# sensie_v_0_0.net
KiCad netlist of a schematic drawn in Altium Designer
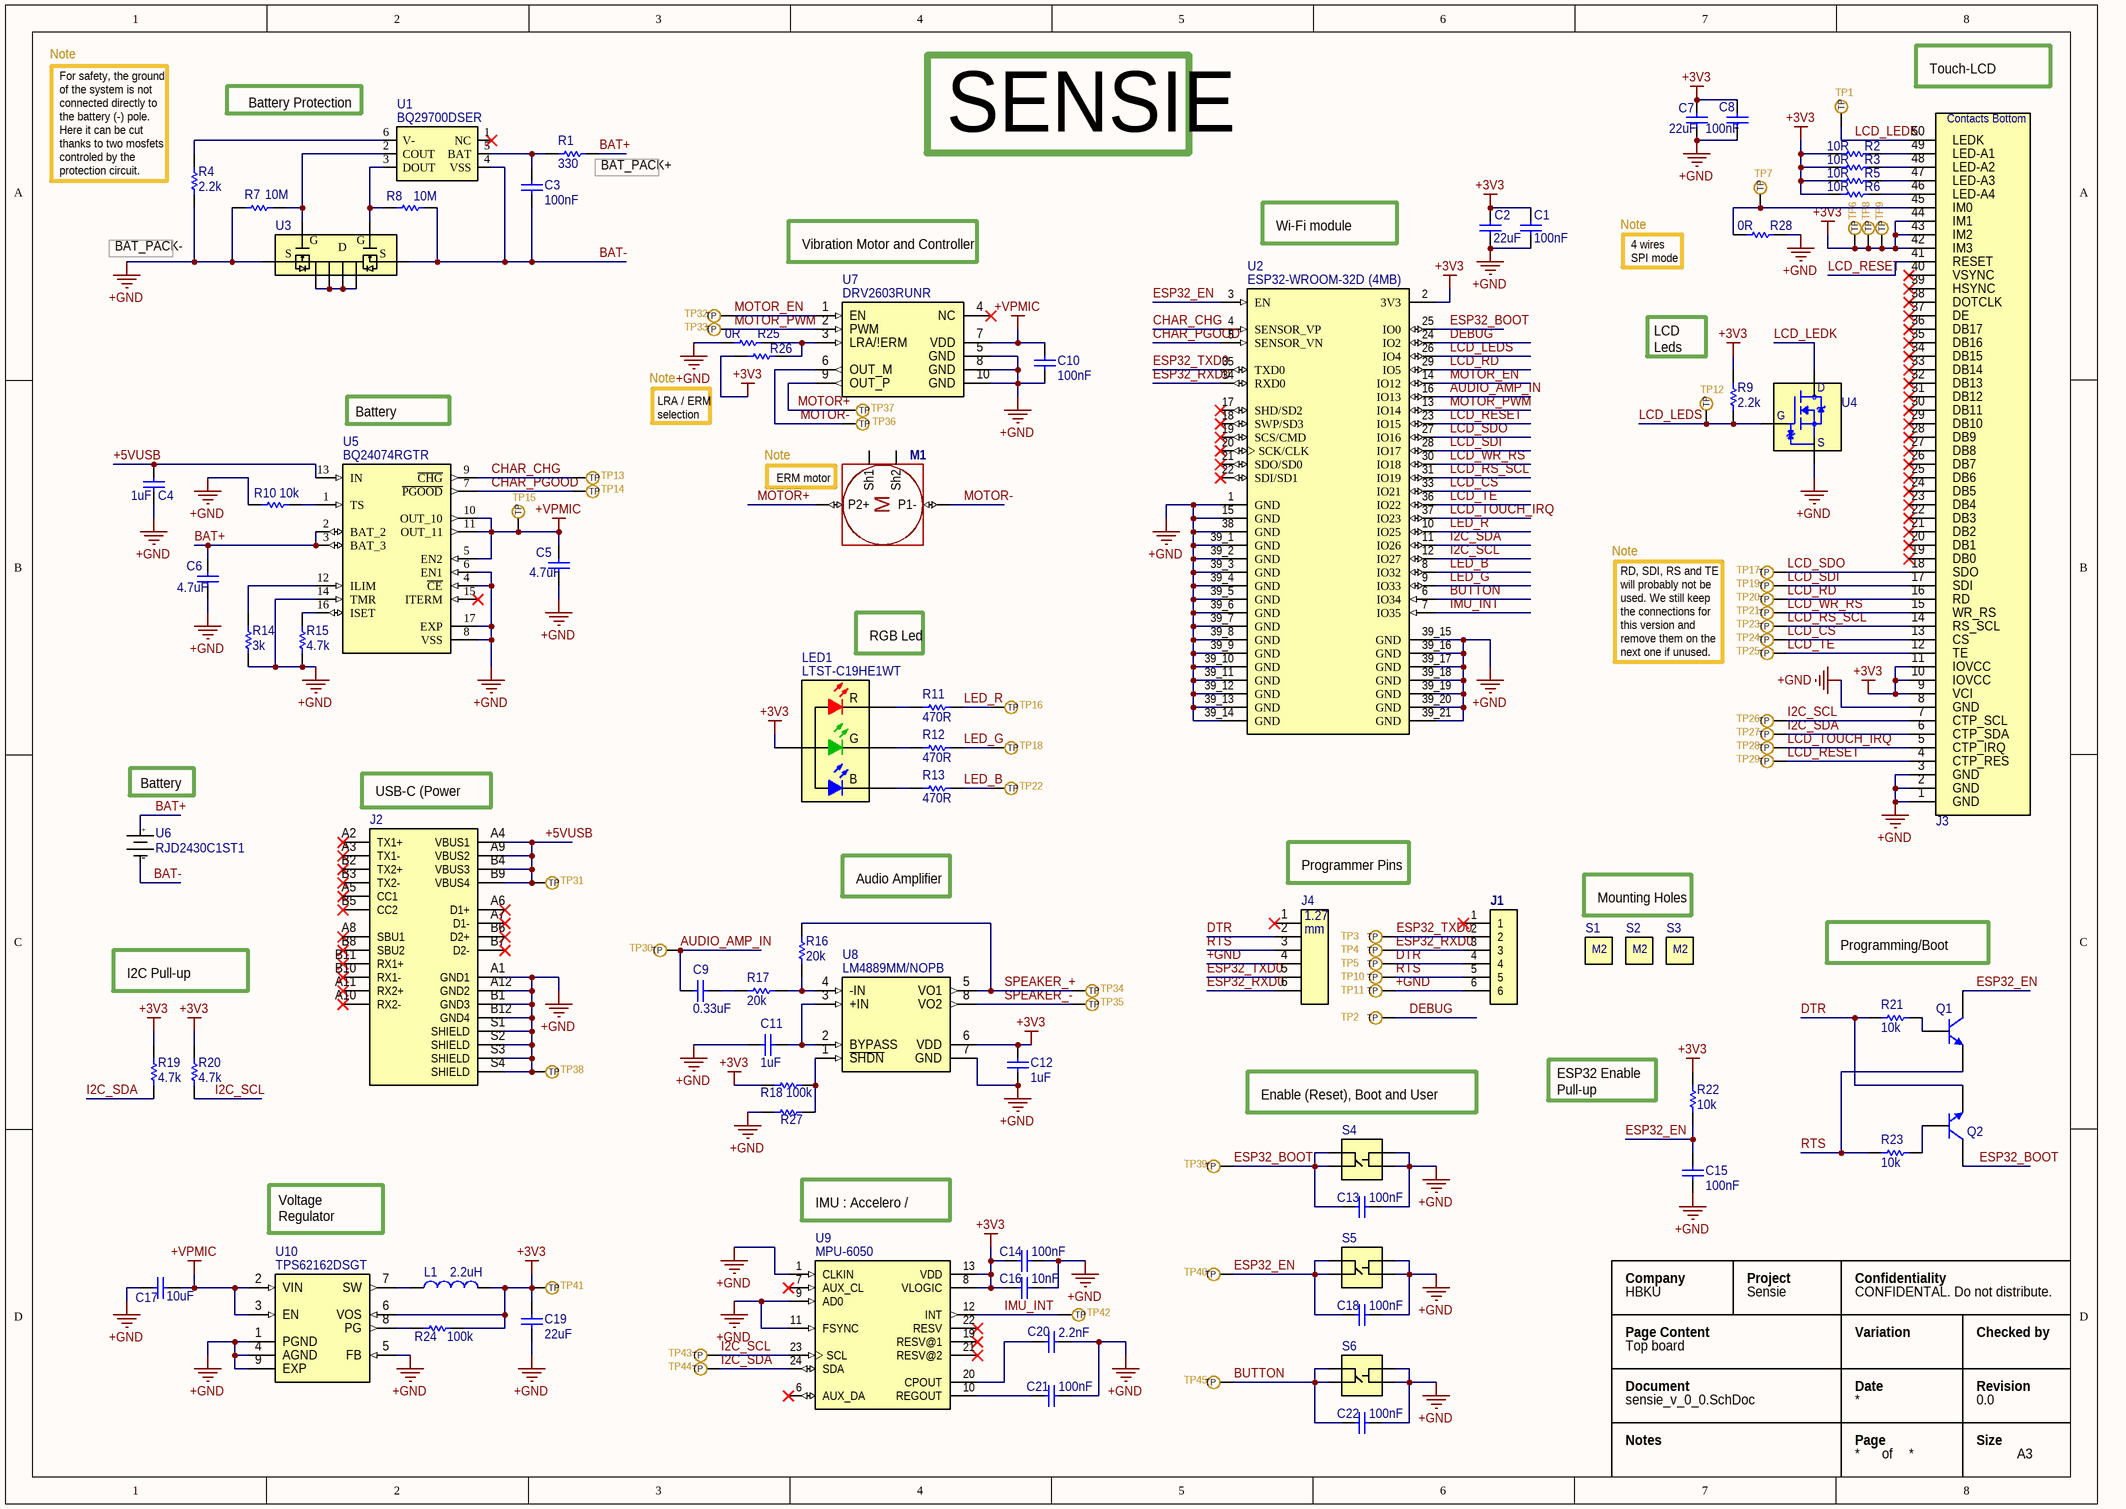
[diagram p0: sensie_v_0_0.SchDoc]

(export (version "E")
  (design (tool "Eeschema 10.0.6"))
  (components
    (comp (ref "C1")
      (value "100nF")
      (footprint "C0402")
      (description "CAP CER 0.1UF 16V X7R 0402")
      (fields
        (field (name "MANUFACTURER PART NUMBER") "GRM155R71C104KA88J")
        (field (name "MANUFACTURER") "Murata Electronics")
      )
      (libsource (lib "rcl") (part "CAP 100nF 0402"))
    )
    (comp (ref "C2")
      (value "22uF")
      (footprint "C0603")
      (description "CAP CER 22UF 6.3V X5R 0603")
      (fields
        (field (name "MANUFACTURER PART NUMBER") "GRM188R60J226MEA0D")
        (field (name "MANUFACTURER") "Murata Electronics")
      )
      (libsource (lib "rcl") (part "CAP 22uF 0603"))
    )
    (comp (ref "C3")
      (value "100nF")
      (footprint "C0402")
      (description "CAP CER 0.1UF 16V X7R 0402")
      (fields
        (field (name "MANUFACTURER PART NUMBER") "GRM155R71C104KA88J")
        (field (name "MANUFACTURER") "Murata Electronics")
      )
      (libsource (lib "rcl") (part "CAP 100nF 0402"))
    )
    (comp (ref "C4")
      (value "1uF")
      (footprint "C0402")
      (description "CAP CER 1UF 10V X6S 0402")
      (fields
        (field (name "MANUFACTURER PART NUMBER") "GRM155C81A105KA12D")
        (field (name "MANUFACTURER") "Murata Electronics")
      )
      (libsource (lib "rcl") (part "CAP 1uF 0402"))
    )
    (comp (ref "C5")
      (value "4.7uF")
      (footprint "C0402")
      (description "CAP CER 4.7UF 6.3V X5R 0402")
      (fields
        (field (name "MANUFACTURER PART NUMBER") "GRM155R60J475ME47D")
        (field (name "MANUFACTURER") "Murata Electronics")
      )
      (libsource (lib "rcl") (part "CAP 4.7uF 0402"))
    )
    (comp (ref "C6")
      (value "4.7uF")
      (footprint "C0402")
      (description "CAP CER 4.7UF 6.3V X5R 0402")
      (fields
        (field (name "MANUFACTURER PART NUMBER") "GRM155R60J475ME47D")
        (field (name "MANUFACTURER") "Murata Electronics")
      )
      (libsource (lib "rcl") (part "CAP 4.7uF 0402"))
    )
    (comp (ref "C7")
      (value "22uF")
      (footprint "C0603")
      (description "CAP CER 22UF 6.3V X5R 0603")
      (fields
        (field (name "MANUFACTURER PART NUMBER") "GRM188R60J226MEA0D")
        (field (name "MANUFACTURER") "Murata Electronics")
      )
      (libsource (lib "rcl") (part "CAP 22uF 0603"))
    )
    (comp (ref "C8")
      (value "100nF")
      (footprint "C0402")
      (description "CAP CER 0.1UF 16V X7R 0402")
      (fields
        (field (name "MANUFACTURER PART NUMBER") "GRM155R71C104KA88J")
        (field (name "MANUFACTURER") "Murata Electronics")
      )
      (libsource (lib "rcl") (part "CAP 100nF 0402"))
    )
    (comp (ref "C9")
      (value "0.33uF")
      (footprint "C0402")
      (description "CAP CER 0.33UF 10V X6S 0402")
      (fields
        (field (name "MANUFACTURER PART NUMBER") "GRM155R61A334KE15D")
        (field (name "MANUFACTURER") "Murata Electronics")
      )
      (libsource (lib "rcl") (part "CAP 0.33uF 0402"))
    )
    (comp (ref "C10")
      (value "100nF")
      (footprint "C0402")
      (description "CAP CER 0.1UF 16V X7R 0402")
      (fields
        (field (name "MANUFACTURER PART NUMBER") "GRM155R71C104KA88J")
        (field (name "MANUFACTURER") "Murata Electronics")
      )
      (libsource (lib "rcl") (part "CAP 100nF 0402"))
    )
    (comp (ref "C11")
      (value "1uF")
      (footprint "C0402")
      (description "CAP CER 1UF 10V X6S 0402")
      (fields
        (field (name "MANUFACTURER PART NUMBER") "GRM155C81A105KA12D")
        (field (name "MANUFACTURER") "Murata Electronics")
      )
      (libsource (lib "rcl") (part "CAP 1uF 0402"))
    )
    (comp (ref "C12")
      (value "1uF")
      (footprint "C0402")
      (description "CAP CER 1UF 10V X6S 0402")
      (fields
        (field (name "MANUFACTURER PART NUMBER") "GRM155C81A105KA12D")
        (field (name "MANUFACTURER") "Murata Electronics")
      )
      (libsource (lib "rcl") (part "CAP 1uF 0402"))
    )
    (comp (ref "C13")
      (value "100nF")
      (footprint "C0402")
      (description "CAP CER 0.1UF 16V X7R 0402")
      (fields
        (field (name "MANUFACTURER PART NUMBER") "GRM155R71C104KA88J")
        (field (name "MANUFACTURER") "Murata Electronics")
      )
      (libsource (lib "rcl") (part "CAP 100nF 0402"))
    )
    (comp (ref "C14")
      (value "100nF")
      (footprint "C0402")
      (description "CAP CER 0.1UF 16V X7R 0402")
      (fields
        (field (name "MANUFACTURER PART NUMBER") "GRM155R71C104KA88J")
        (field (name "MANUFACTURER") "Murata Electronics")
      )
      (libsource (lib "rcl") (part "CAP 100nF 0402"))
    )
    (comp (ref "C15")
      (value "100nF")
      (footprint "C0402")
      (description "CAP CER 0.1UF 16V X7R 0402")
      (fields
        (field (name "MANUFACTURER PART NUMBER") "GRM155R71C104KA88J")
        (field (name "MANUFACTURER") "Murata Electronics")
      )
      (libsource (lib "rcl") (part "CAP 100nF 0402"))
    )
    (comp (ref "C16")
      (value "10nF")
      (footprint "C0402")
      (description "CAP CER 10nF 16V X7R 0402")
      (fields
        (field (name "MANUFACTURER PART NUMBER") "GCM155R71H103KA55D")
        (field (name "MANUFACTURER") "Murata Electronics")
      )
      (libsource (lib "rcl") (part "CAP 10nF 0402"))
    )
    (comp (ref "C17")
      (value "10uF")
      (footprint "C0402")
      (description "CAP CER 10UF 4V X5R 0402")
      (fields
        (field (name "MANUFACTURER PART NUMBER") "GRM155R60G106ME44D")
        (field (name "MANUFACTURER") "Murata Electronics")
      )
      (libsource (lib "rcl") (part "CAP 10uF 0402"))
    )
    (comp (ref "C18")
      (value "100nF")
      (footprint "C0402")
      (description "CAP CER 0.1UF 16V X7R 0402")
      (fields
        (field (name "MANUFACTURER PART NUMBER") "GRM155R71C104KA88J")
        (field (name "MANUFACTURER") "Murata Electronics")
      )
      (libsource (lib "rcl") (part "CAP 100nF 0402"))
    )
    (comp (ref "C19")
      (value "22uF")
      (footprint "C0603")
      (description "CAP CER 22UF 6.3V X5R 0603")
      (fields
        (field (name "MANUFACTURER PART NUMBER") "GRM188R60J226MEA0D")
        (field (name "MANUFACTURER") "Murata Electronics")
      )
      (libsource (lib "rcl") (part "CAP 22uF 0603"))
    )
    (comp (ref "C20")
      (value "2.2nF")
      (footprint "C0402")
      (description "CAP CER 2.2nF 16V X7R 0402")
      (fields
        (field (name "MANUFACTURER PART NUMBER") "GCM155R72A222KA37D")
        (field (name "MANUFACTURER") "Murata Electronics")
      )
      (libsource (lib "rcl") (part "CAP 2.2nF 0402"))
    )
    (comp (ref "C21")
      (value "100nF")
      (footprint "C0402")
      (description "CAP CER 0.1UF 16V X7R 0402")
      (fields
        (field (name "MANUFACTURER PART NUMBER") "GRM155R71C104KA88J")
        (field (name "MANUFACTURER") "Murata Electronics")
      )
      (libsource (lib "rcl") (part "CAP 100nF 0402"))
    )
    (comp (ref "C22")
      (value "100nF")
      (footprint "C0402")
      (description "CAP CER 0.1UF 16V X7R 0402")
      (fields
        (field (name "MANUFACTURER PART NUMBER") "GRM155R71C104KA88J")
        (field (name "MANUFACTURER") "Murata Electronics")
      )
      (libsource (lib "rcl") (part "CAP 100nF 0402"))
    )
    (comp (ref "J1")
      (value "Plug of Nails 6 pins")
      (footprint "PLUG-OF-NAILS-6-PIN")
      (description "CBL PLUG-OF-NAILS 6-PIN with NO ATTACHMENT holes (contrary to the digikey link)")
      (fields
        (field (name "MANUFACTURER") "Tag-Connect LLC")
        (field (name "MANUFACTURER PART NUMBER") "TC2030-CTX")
      )
      (libsource (lib "connectors") (part "Plug of Nails 6 pins"))
    )
    (comp (ref "J2")
      (value "1054500101")
      (footprint "USB-C-1054500101")
      (description "USB-C CONN RCP USB3.1 TYPEC 24P SMD RA")
      (fields (field (name "MANUFACTURER") "Molex"))
      (libsource (lib "connectors") (part "1054500101"))
    )
    (comp (ref "J3")
      (value "FPC-50-screen-connector-bottom-62684-501100ALF")
      (footprint "FPC-50-62684-501100ALF")
      (description "FPC CONN BOTTOM 50POS 0.50MM R/A")
      (fields
        (field (name "MANUFACTURER") "Amphenol ICC (FCI)")
        (field (name "MANUFACTURER PART NUMBER") "62684-501100ALF")
      )
      (libsource (lib "connectors") (part "FPC-50-screen-connector-bottom-62684-501100ALF"))
    )
    (comp (ref "J4")
      (value "FTS-103-01-F-DV-TR")
      (footprint "CON_6_2_1.27_FTS_103_01")
      (description "CONN HEADER SMD 6POS 1.27MM")
      (fields (field (name "MANUFACTURER") "Samtec Inc."))
      (libsource (lib "connectors") (part "FTS-103-01-F-DV-TR"))
    )
    (comp (ref "L1")
      (value "2.2uH")
      (footprint "L0603")
      (description "2.2UH20% 1.05A(MAX) / 1.15A(TYP.")
      (fields
        (field (name "MANUFACTURER") "Murata Electronics")
        (field (name "MANUFACTURER PART NUMBER") "LQM18PN2R2MGHD")
      )
      (libsource (lib "rcl") (part "IND 2.2uH 0603"))
    )
    (comp (ref "LED1")
      (value "rgb_LTST-C19HE1WT")
      (footprint "LTST-C19HE1WT-4_V")
      (fields
        (field (name "MANUFACTURER") "Lite-On Inc.")
        (field (name "MANUFACTURER PART NUMBER") "LTST-C19HE1WT")
      )
      (libsource (lib "chips") (part "rgb_LTST-C19HE1WT"))
    )
    (comp (ref "M1")
      (value "MOTOR")
      (footprint "MOTOR")
      (description "VIBRATION MOTOR CYL 3V SMD")
      (fields
        (field (name "MANUFACTURER") "Jinlong Machinery & Electronics, Inc.")
        (field (name "MANUFACTURER PART NUMBER") "Z4FC1B1301781")
      )
      (libsource (lib "miscellaneaous") (part "MOTOR"))
    )
    (comp (ref "Q1")
      (value "MMBT2222ALT1G")
      (footprint "ONSC-SOT-23-3-318-08_V")
      (fields (field (name "MANUFACTURER") "ON Semiconductor"))
      (libsource (lib "chips") (part "MMBT2222ALT1G"))
    )
    (comp (ref "Q2")
      (value "MMBT2222ALT1G")
      (footprint "ONSC-SOT-23-3-318-08_V")
      (fields (field (name "MANUFACTURER") "ON Semiconductor"))
      (libsource (lib "chips") (part "MMBT2222ALT1G"))
    )
    (comp (ref "R1")
      (value "330")
      (footprint "R0402")
      (description "RES SMD 330 OHM 1% 1/16W 0402")
      (fields
        (field (name "MANUFACTURER") "Yageo")
        (field (name "MANUFACTURER PART NUMBER") "RC0402FR-07330RL")
      )
      (libsource (lib "rcl") (part "RES 330R 0402"))
    )
    (comp (ref "R2")
      (value "10R")
      (footprint "R0402")
      (description "RES SMD 10 OHM 1% 1/16W 0402")
      (fields
        (field (name "MANUFACTURER") "Yageo")
        (field (name "MANUFACTURER PART NUMBER") "RC0402FR-0710RL")
      )
      (libsource (lib "rcl") (part "RES 10R 0402"))
    )
    (comp (ref "R3")
      (value "10R")
      (footprint "R0402")
      (description "RES SMD 10 OHM 1% 1/16W 0402")
      (fields
        (field (name "MANUFACTURER") "Yageo")
        (field (name "MANUFACTURER PART NUMBER") "RC0402FR-0710RL")
      )
      (libsource (lib "rcl") (part "RES 10R 0402"))
    )
    (comp (ref "R4")
      (value "2.2k")
      (footprint "R0402")
      (description "RES SMD 2.2K OHM 1% 1/16W 0402")
      (fields
        (field (name "MANUFACTURER") "Yageo")
        (field (name "MANUFACTURER PART NUMBER") "RC0402FR-072K2L")
      )
      (libsource (lib "rcl") (part "RES 2.2k 0402"))
    )
    (comp (ref "R5")
      (value "10R")
      (footprint "R0402")
      (description "RES SMD 10 OHM 1% 1/16W 0402")
      (fields
        (field (name "MANUFACTURER") "Yageo")
        (field (name "MANUFACTURER PART NUMBER") "RC0402FR-0710RL")
      )
      (libsource (lib "rcl") (part "RES 10R 0402"))
    )
    (comp (ref "R6")
      (value "10R")
      (footprint "R0402")
      (description "RES SMD 10 OHM 1% 1/16W 0402")
      (fields
        (field (name "MANUFACTURER") "Yageo")
        (field (name "MANUFACTURER PART NUMBER") "RC0402FR-0710RL")
      )
      (libsource (lib "rcl") (part "RES 10R 0402"))
    )
    (comp (ref "R7")
      (value "10M")
      (footprint "R0402")
      (description "RES SMD 10 MOHM 1% 1/16W 0402")
      (fields
        (field (name "MANUFACTURER") "Yageo")
        (field (name "MANUFACTURER PART NUMBER") "RC0402FR-0710ML")
      )
      (libsource (lib "rcl") (part "RES 10M 0402"))
    )
    (comp (ref "R8")
      (value "10M")
      (footprint "R0402")
      (description "RES SMD 10 MOHM 1% 1/16W 0402")
      (fields
        (field (name "MANUFACTURER") "Yageo")
        (field (name "MANUFACTURER PART NUMBER") "RC0402FR-0710ML")
      )
      (libsource (lib "rcl") (part "RES 10M 0402"))
    )
    (comp (ref "R9")
      (value "2.2k")
      (footprint "R0402")
      (description "RES SMD 2.2K OHM 1% 1/16W 0402")
      (fields
        (field (name "MANUFACTURER") "Yageo")
        (field (name "MANUFACTURER PART NUMBER") "RC0402FR-072K2L")
      )
      (libsource (lib "rcl") (part "RES 2.2k 0402"))
    )
    (comp (ref "R10")
      (value "10k")
      (footprint "R0402")
      (description "RES SMD 10K OHM 1% 1/16W 0402")
      (fields
        (field (name "MANUFACTURER") "Yageo")
        (field (name "MANUFACTURER PART NUMBER") "RC0402FR-0710KL")
      )
      (libsource (lib "rcl") (part "RES 10k 0402"))
    )
    (comp (ref "R11")
      (value "470R")
      (footprint "R0402")
      (description "RES SMD 470 OHM 1% 1/16W 0402")
      (fields
        (field (name "MANUFACTURER") "Yageo")
        (field (name "MANUFACTURER PART NUMBER") "RC0402FR-07470RL")
      )
      (libsource (lib "rcl") (part "RES 470R 0402"))
    )
    (comp (ref "R12")
      (value "470R")
      (footprint "R0402")
      (description "RES SMD 470 OHM 1% 1/16W 0402")
      (fields
        (field (name "MANUFACTURER") "Yageo")
        (field (name "MANUFACTURER PART NUMBER") "RC0402FR-07470RL")
      )
      (libsource (lib "rcl") (part "RES 470R 0402"))
    )
    (comp (ref "R13")
      (value "470R")
      (footprint "R0402")
      (description "RES SMD 470 OHM 1% 1/16W 0402")
      (fields
        (field (name "MANUFACTURER") "Yageo")
        (field (name "MANUFACTURER PART NUMBER") "RC0402FR-07470RL")
      )
      (libsource (lib "rcl") (part "RES 470R 0402"))
    )
    (comp (ref "R14")
      (value "3k")
      (footprint "R0402")
      (description "RES SMD 10K OHM 1% 1/16W 0402")
      (fields
        (field (name "MANUFACTURER") "Yageo")
        (field (name "MANUFACTURER PART NUMBER") "RC0402FR-073KL")
      )
      (libsource (lib "rcl") (part "RES 3k 0402"))
    )
    (comp (ref "R15")
      (value "4.7k")
      (footprint "R0402")
      (description "RES SMD 4.7K OHM 1% 1/16W 0402")
      (fields
        (field (name "MANUFACTURER") "Yageo")
        (field (name "MANUFACTURER PART NUMBER") "RT0402FRE074K7L")
      )
      (libsource (lib "rcl") (part "RES 4.7k 0402"))
    )
    (comp (ref "R16")
      (value "20k")
      (footprint "R0402")
      (description "RES SMD 20K OHM 1% 1/16W 0402")
      (fields
        (field (name "MANUFACTURER") "Yageo")
        (field (name "MANUFACTURER PART NUMBER") "RC0402FR-0720KL")
      )
      (libsource (lib "rcl") (part "RES 20k 0402"))
    )
    (comp (ref "R17")
      (value "20k")
      (footprint "R0402")
      (description "RES SMD 20K OHM 1% 1/16W 0402")
      (fields
        (field (name "MANUFACTURER") "Yageo")
        (field (name "MANUFACTURER PART NUMBER") "RC0402FR-0720KL")
      )
      (libsource (lib "rcl") (part "RES 20k 0402"))
    )
    (comp (ref "R18")
      (value "100k")
      (footprint "R0402")
      (description "RES SMD 100K OHM 1% 1/16W 0402")
      (fields
        (field (name "MANUFACTURER") "Yageo")
        (field (name "MANUFACTURER PART NUMBER") "RC0402FR-07100KL")
      )
      (libsource (lib "rcl") (part "RES 100k 0402"))
    )
    (comp (ref "R19")
      (value "4.7k")
      (footprint "R0402")
      (description "RES SMD 4.7K OHM 1% 1/16W 0402")
      (fields
        (field (name "MANUFACTURER") "Yageo")
        (field (name "MANUFACTURER PART NUMBER") "RT0402FRE074K7L")
      )
      (libsource (lib "rcl") (part "RES 4.7k 0402"))
    )
    (comp (ref "R20")
      (value "4.7k")
      (footprint "R0402")
      (description "RES SMD 4.7K OHM 1% 1/16W 0402")
      (fields
        (field (name "MANUFACTURER") "Yageo")
        (field (name "MANUFACTURER PART NUMBER") "RT0402FRE074K7L")
      )
      (libsource (lib "rcl") (part "RES 4.7k 0402"))
    )
    (comp (ref "R21")
      (value "10k")
      (footprint "R0402")
      (description "RES SMD 10K OHM 1% 1/16W 0402")
      (fields
        (field (name "MANUFACTURER") "Yageo")
        (field (name "MANUFACTURER PART NUMBER") "RC0402FR-0710KL")
      )
      (libsource (lib "rcl") (part "RES 10k 0402"))
    )
    (comp (ref "R22")
      (value "10k")
      (footprint "R0402")
      (description "RES SMD 10K OHM 1% 1/16W 0402")
      (fields
        (field (name "MANUFACTURER") "Yageo")
        (field (name "MANUFACTURER PART NUMBER") "RC0402FR-0710KL")
      )
      (libsource (lib "rcl") (part "RES 10k 0402"))
    )
    (comp (ref "R23")
      (value "10k")
      (footprint "R0402")
      (description "RES SMD 10K OHM 1% 1/16W 0402")
      (fields
        (field (name "MANUFACTURER") "Yageo")
        (field (name "MANUFACTURER PART NUMBER") "RC0402FR-0710KL")
      )
      (libsource (lib "rcl") (part "RES 10k 0402"))
    )
    (comp (ref "R24")
      (value "100k")
      (footprint "R0402")
      (description "RES SMD 100K OHM 1% 1/16W 0402")
      (fields
        (field (name "MANUFACTURER") "Yageo")
        (field (name "MANUFACTURER PART NUMBER") "RC0402FR-07100KL")
      )
      (libsource (lib "rcl") (part "RES 100k 0402"))
    )
    (comp (ref "R25")
      (value "0R")
      (footprint "R0402")
      (description "RES SMD 0 OHM JUMPER 1/16W 0402")
      (fields
        (field (name "MANUFACTURER") "Yageo")
        (field (name "MANUFACTURER PART NUMBER") "RC0402JR-070RL")
      )
      (libsource (lib "rcl") (part "RES 0R 0402"))
    )
    (comp (ref "R26")
      (value "Thick Film")
      (footprint "R0402_DNI")
      (description "DNI (Do Not Install)")
      (libsource (lib "rcl") (part "RES DNI 0402"))
    )
    (comp (ref "R27")
      (value "Thick Film")
      (footprint "R0402_DNI")
      (description "DNI (Do Not Install)")
      (libsource (lib "rcl") (part "RES DNI 0402"))
    )
    (comp (ref "R28")
      (value "0R")
      (footprint "R0402")
      (description "RES SMD 0 OHM JUMPER 1/16W 0402")
      (fields
        (field (name "MANUFACTURER") "Yageo")
        (field (name "MANUFACTURER PART NUMBER") "RC0402JR-070RL")
      )
      (libsource (lib "rcl") (part "RES 0R 0402"))
    )
    (comp (ref "S1")
      (value "hole_M2")
      (footprint "M2_no_screw")
      (description "Mounting hole  M2 size, no solder stop, so no screw")
      (libsource (lib "connectors") (part "hole_M2"))
    )
    (comp (ref "S2")
      (value "hole_M2")
      (footprint "M2_no_screw")
      (description "Mounting hole  M2 size, no solder stop, so no screw")
      (libsource (lib "connectors") (part "hole_M2"))
    )
    (comp (ref "S3")
      (value "hole_M2")
      (footprint "M2_no_screw")
      (description "Mounting hole  M2 size, no solder stop, so no screw")
      (libsource (lib "connectors") (part "hole_M2"))
    )
    (comp (ref "S4")
      (value "TL1014BF160QG")
      (footprint "BUTTON_TL1014BF160QG")
      (description "SWITCH TACTILE SPST-NO 0.05A 12V")
      (fields (field (name "MANUFACTURER") "E-Switch"))
      (libsource (lib "miscellaneaous") (part "TL1014BF160QG"))
    )
    (comp (ref "S5")
      (value "TL1014BF160QG")
      (footprint "BUTTON_TL1014BF160QG")
      (description "SWITCH TACTILE SPST-NO 0.05A 12V")
      (fields (field (name "MANUFACTURER") "E-Switch"))
      (libsource (lib "miscellaneaous") (part "TL1014BF160QG"))
    )
    (comp (ref "S6")
      (value "TL1014BF160QG")
      (footprint "BUTTON_TL1014BF160QG")
      (description "SWITCH TACTILE SPST-NO 0.05A 12V")
      (fields (field (name "MANUFACTURER") "E-Switch"))
      (libsource (lib "miscellaneaous") (part "TL1014BF160QG"))
    )
    (comp (ref "TP1")
      (value "TP_1mm")
      (footprint "TP_1mm")
      (description "Test point 1mm diameter")
      (libsource (lib "miscellaneaous") (part "TP_1mm"))
    )
    (comp (ref "TP2")
      (value "TP_2mm")
      (footprint "TP_2mm")
      (description "Test point 2mm diameter")
      (libsource (lib "miscellaneaous") (part "TP_2mm"))
    )
    (comp (ref "TP3")
      (value "TP_2mm")
      (footprint "TP_2mm")
      (description "Test point 2mm diameter")
      (libsource (lib "miscellaneaous") (part "TP_2mm"))
    )
    (comp (ref "TP4")
      (value "TP_2mm")
      (footprint "TP_2mm")
      (description "Test point 2mm diameter")
      (libsource (lib "miscellaneaous") (part "TP_2mm"))
    )
    (comp (ref "TP5")
      (value "TP_2mm")
      (footprint "TP_2mm")
      (description "Test point 2mm diameter")
      (libsource (lib "miscellaneaous") (part "TP_2mm"))
    )
    (comp (ref "TP6")
      (value "TP_1mm")
      (footprint "TP_1mm")
      (description "Test point 1mm diameter")
      (libsource (lib "miscellaneaous") (part "TP_1mm"))
    )
    (comp (ref "TP7")
      (value "TP_1mm")
      (footprint "TP_1mm")
      (description "Test point 1mm diameter")
      (libsource (lib "miscellaneaous") (part "TP_1mm"))
    )
    (comp (ref "TP8")
      (value "TP_1mm")
      (footprint "TP_1mm")
      (description "Test point 1mm diameter")
      (libsource (lib "miscellaneaous") (part "TP_1mm"))
    )
    (comp (ref "TP9")
      (value "TP_1mm")
      (footprint "TP_1mm")
      (description "Test point 1mm diameter")
      (libsource (lib "miscellaneaous") (part "TP_1mm"))
    )
    (comp (ref "TP10")
      (value "TP_2mm")
      (footprint "TP_2mm")
      (description "Test point 2mm diameter")
      (libsource (lib "miscellaneaous") (part "TP_2mm"))
    )
    (comp (ref "TP11")
      (value "TP_2mm")
      (footprint "TP_2mm")
      (description "Test point 2mm diameter")
      (libsource (lib "miscellaneaous") (part "TP_2mm"))
    )
    (comp (ref "TP12")
      (value "TP_1mm")
      (footprint "TP_1mm")
      (description "Test point 1mm diameter")
      (libsource (lib "miscellaneaous") (part "TP_1mm"))
    )
    (comp (ref "TP13")
      (value "TP_1mm")
      (footprint "TP_1mm")
      (description "Test point 1mm diameter")
      (libsource (lib "miscellaneaous") (part "TP_1mm"))
    )
    (comp (ref "TP14")
      (value "TP_1mm")
      (footprint "TP_1mm")
      (description "Test point 1mm diameter")
      (libsource (lib "miscellaneaous") (part "TP_1mm"))
    )
    (comp (ref "TP15")
      (value "TP_1mm")
      (footprint "TP_1mm")
      (description "Test point 1mm diameter")
      (libsource (lib "miscellaneaous") (part "TP_1mm"))
    )
    (comp (ref "TP16")
      (value "TP_1mm")
      (footprint "TP_1mm")
      (description "Test point 1mm diameter")
      (libsource (lib "miscellaneaous") (part "TP_1mm"))
    )
    (comp (ref "TP17")
      (value "TP_1mm")
      (footprint "TP_1mm")
      (description "Test point 1mm diameter")
      (libsource (lib "miscellaneaous") (part "TP_1mm"))
    )
    (comp (ref "TP18")
      (value "TP_1mm")
      (footprint "TP_1mm")
      (description "Test point 1mm diameter")
      (libsource (lib "miscellaneaous") (part "TP_1mm"))
    )
    (comp (ref "TP19")
      (value "TP_1mm")
      (footprint "TP_1mm")
      (description "Test point 1mm diameter")
      (libsource (lib "miscellaneaous") (part "TP_1mm"))
    )
    (comp (ref "TP20")
      (value "TP_1mm")
      (footprint "TP_1mm")
      (description "Test point 1mm diameter")
      (libsource (lib "miscellaneaous") (part "TP_1mm"))
    )
    (comp (ref "TP21")
      (value "TP_1mm")
      (footprint "TP_1mm")
      (description "Test point 1mm diameter")
      (libsource (lib "miscellaneaous") (part "TP_1mm"))
    )
    (comp (ref "TP22")
      (value "TP_1mm")
      (footprint "TP_1mm")
      (description "Test point 1mm diameter")
      (libsource (lib "miscellaneaous") (part "TP_1mm"))
    )
    (comp (ref "TP23")
      (value "TP_1mm")
      (footprint "TP_1mm")
      (description "Test point 1mm diameter")
      (libsource (lib "miscellaneaous") (part "TP_1mm"))
    )
    (comp (ref "TP24")
      (value "TP_1mm")
      (footprint "TP_1mm")
      (description "Test point 1mm diameter")
      (libsource (lib "miscellaneaous") (part "TP_1mm"))
    )
    (comp (ref "TP25")
      (value "TP_1mm")
      (footprint "TP_1mm")
      (description "Test point 1mm diameter")
      (libsource (lib "miscellaneaous") (part "TP_1mm"))
    )
    (comp (ref "TP26")
      (value "TP_1mm")
      (footprint "TP_1mm")
      (description "Test point 1mm diameter")
      (libsource (lib "miscellaneaous") (part "TP_1mm"))
    )
    (comp (ref "TP27")
      (value "TP_1mm")
      (footprint "TP_1mm")
      (description "Test point 1mm diameter")
      (libsource (lib "miscellaneaous") (part "TP_1mm"))
    )
    (comp (ref "TP28")
      (value "TP_1mm")
      (footprint "TP_1mm")
      (description "Test point 1mm diameter")
      (libsource (lib "miscellaneaous") (part "TP_1mm"))
    )
    (comp (ref "TP29")
      (value "TP_1mm")
      (footprint "TP_1mm")
      (description "Test point 1mm diameter")
      (libsource (lib "miscellaneaous") (part "TP_1mm"))
    )
    (comp (ref "TP30")
      (value "TP_1mm")
      (footprint "TP_1mm")
      (description "Test point 1mm diameter")
      (libsource (lib "miscellaneaous") (part "TP_1mm"))
    )
    (comp (ref "TP31")
      (value "TP_1mm")
      (footprint "TP_1mm")
      (description "Test point 1mm diameter")
      (libsource (lib "miscellaneaous") (part "TP_1mm"))
    )
    (comp (ref "TP32")
      (value "TP_1mm")
      (footprint "TP_1mm")
      (description "Test point 1mm diameter")
      (libsource (lib "miscellaneaous") (part "TP_1mm"))
    )
    (comp (ref "TP33")
      (value "TP_1mm")
      (footprint "TP_1mm")
      (description "Test point 1mm diameter")
      (libsource (lib "miscellaneaous") (part "TP_1mm"))
    )
    (comp (ref "TP34")
      (value "TP_2mm")
      (footprint "TP_2mm")
      (description "Test point 2mm diameter")
      (libsource (lib "miscellaneaous") (part "TP_2mm"))
    )
    (comp (ref "TP35")
      (value "TP_2mm")
      (footprint "TP_2mm")
      (description "Test point 2mm diameter")
      (libsource (lib "miscellaneaous") (part "TP_2mm"))
    )
    (comp (ref "TP36")
      (value "TP_2mm")
      (footprint "TP_2mm")
      (description "Test point 2mm diameter")
      (libsource (lib "miscellaneaous") (part "TP_2mm"))
    )
    (comp (ref "TP37")
      (value "TP_2mm")
      (footprint "TP_2mm")
      (description "Test point 2mm diameter")
      (libsource (lib "miscellaneaous") (part "TP_2mm"))
    )
    (comp (ref "TP38")
      (value "TP_1mm")
      (footprint "TP_1mm")
      (description "Test point 1mm diameter")
      (libsource (lib "miscellaneaous") (part "TP_1mm"))
    )
    (comp (ref "TP39")
      (value "TP_1mm")
      (footprint "TP_1mm")
      (description "Test point 1mm diameter")
      (libsource (lib "miscellaneaous") (part "TP_1mm"))
    )
    (comp (ref "TP40")
      (value "TP_1mm")
      (footprint "TP_1mm")
      (description "Test point 1mm diameter")
      (libsource (lib "miscellaneaous") (part "TP_1mm"))
    )
    (comp (ref "TP41")
      (value "TP_1mm")
      (footprint "TP_1mm")
      (description "Test point 1mm diameter")
      (libsource (lib "miscellaneaous") (part "TP_1mm"))
    )
    (comp (ref "TP42")
      (value "TP_1mm")
      (footprint "TP_1mm")
      (description "Test point 1mm diameter")
      (libsource (lib "miscellaneaous") (part "TP_1mm"))
    )
    (comp (ref "TP43")
      (value "TP_1mm")
      (footprint "TP_1mm")
      (description "Test point 1mm diameter")
      (libsource (lib "miscellaneaous") (part "TP_1mm"))
    )
    (comp (ref "TP44")
      (value "TP_1mm")
      (footprint "TP_1mm")
      (description "Test point 1mm diameter")
      (libsource (lib "miscellaneaous") (part "TP_1mm"))
    )
    (comp (ref "TP45")
      (value "TP_1mm")
      (footprint "TP_1mm")
      (description "Test point 1mm diameter")
      (libsource (lib "miscellaneaous") (part "TP_1mm"))
    )
    (comp (ref "U1")
      (value "BQ29700DSER")
      (footprint "BATT_PROTEC_BQ29700DSER")
      (description "BATT LITHIUM BATT PROTECT 6-SON")
      (fields (field (name "MANUFACTURER") "Texas Instruments"))
      (libsource (lib "chips") (part "BQ29700DSER"))
    )
    (comp (ref "U2")
      (value "ESP32-WROOM-32D")
      (footprint "ESP32-WROOM-32D (4MB)")
      (description "ESP32-WROOM-32D Wifi/Bluetooth Module")
      (fields
        (field (name "MANUFACTURER") "Espressif Systems")
        (field (name "MANUFACTURER PART NUMBER") "ESP32-WROOM-32D (4MB)")
      )
      (libsource (lib "chips") (part "ESP32-WROOM-32D"))
    )
    (comp (ref "U3")
      (value "ECH8693R-TL-W")
      (footprint "MOSFET_2CHAN_ECH8693R-TL-W")
      (description "MOSFET 2N-CH 24V 14A SOT-28")
      (fields (field (name "MANUFACTURER") "ON Semiconductor"))
      (libsource (lib "chips") (part "ECH8693R-TL-W"))
    )
    (comp (ref "U4")
      (value "DMG1012UW-7")
      (footprint "MOSFET-DMG1012UW-SOT323")
      (description "MOSFET Logi level N-CH 20V 1A SOT323")
      (fields (field (name "MANUFACTURER") "Diodes Incorporated"))
      (libsource (lib "chips") (part "DMG1012UW-7"))
    )
    (comp (ref "U5")
      (value "BQ24074RGTR")
      (footprint "BATT_CHARG_BQ24074RGTR")
      (description "BATT LI-ION CHARGE MGMT 16-QFN")
      (fields
        (field (name "MANUFACTURER") "Texas Instruments")
        (field (name "MANUFACTURER PART NUMBER") "BQ24074RGTR")
      )
      (libsource (lib "chips") (part "BQ24074RGTR"))
    )
    (comp (ref "U6")
      (value "RJD2430C1ST1")
      (footprint "COIN_BAT_110_MAH_RJD2430C1ST1")
      (description "BATTERY LITHIUM 110mAh 3.7V COIN 24.5MM")
      (fields
        (field (name "MANUFACTURER") "Illinois Capacitor")
        (field (name "MANUFACTURER PART NUMBER") "RJD2430C1ST1")
      )
      (libsource (lib "miscellaneaous") (part "RJD2430C1ST1"))
    )
    (comp (ref "U7")
      (value "DRV2603RUNR")
      (footprint "MOT_DRV_DRV2603RUNR")
      (description "MOTOR DRIVER 2.5V-5.2V 10QFN")
      (fields (field (name "MANUFACTURER") "Texas Instruments"))
      (libsource (lib "chips") (part "DRV2603RUNR"))
    )
    (comp (ref "U8")
      (value "LM4889")
      (footprint "Amp_LM4889MM")
      (description "IC AMP CLASS AB MONO 1W 8VSSOP")
      (fields
        (field (name "MANUFACTURER") "Texas Instruments")
        (field (name "MANUFACTURER PART NUMBER") "LM4889MM/NOPB")
      )
      (libsource (lib "chips") (part "LM4889"))
    )
    (comp (ref "U9")
      (value "MPU-6050")
      (footprint "MPU6050-ACCELERO-GYRO")
      (description "IMU ACCEL/GYRO 3-AXIS I2C 24QFN")
      (fields
        (field (name "MANUFACTURER") "TDK InvenSense")
        (field (name "MANUFACTURER PART NUMBER") "MPU-6050")
      )
      (libsource (lib "chips") (part "MPU-6050"))
    )
    (comp (ref "U10")
      (value "TPS62162DSGT")
      (footprint "REG_BUCK_TPS62162DSGT")
      (description "IC REG BUCK 3.3V 1A 8WSON")
      (fields
        (field (name "MANUFACTURER") "Texas Instruments")
        (field (name "MANUFACTURER PART NUMBER") "TPS62162DSGT")
      )
      (libsource (lib "chips") (part "TPS62162DSGT"))
    )
  )
  (nets
    (net (code "1") (name "+3V3") (class "Default")
      (node (ref "C1") (pin "2") (pinfunction "2_2") (pintype "passive"))
      (node (ref "C12") (pin "2") (pinfunction "2_2") (pintype "passive"))
      (node (ref "C14") (pin "1") (pinfunction "1_1") (pintype "passive"))
      (node (ref "C16") (pin "1") (pinfunction "1_1") (pintype "passive"))
      (node (ref "C19") (pin "2") (pinfunction "2_2") (pintype "passive"))
      (node (ref "C2") (pin "2") (pinfunction "2_2") (pintype "passive"))
      (node (ref "C7") (pin "2") (pinfunction "2_2") (pintype "passive"))
      (node (ref "C8") (pin "2") (pinfunction "2_2") (pintype "passive"))
      (node (ref "J3") (pin "10") (pinfunction "IOVCC_10") (pintype "passive"))
      (node (ref "J3") (pin "11") (pinfunction "IOVCC_11") (pintype "passive"))
      (node (ref "J3") (pin "42") (pinfunction "IM3_42") (pintype "passive"))
      (node (ref "J3") (pin "43") (pinfunction "IM2_43") (pintype "passive"))
      (node (ref "J3") (pin "44") (pinfunction "IM1_44") (pintype "passive"))
      (node (ref "J3") (pin "9") (pinfunction "VCI_9") (pintype "passive"))
      (node (ref "L1") (pin "2") (pinfunction "2_2") (pintype "passive"))
      (node (ref "LED1") (pin "4") (pinfunction "A_4") (pintype "passive"))
      (node (ref "R18") (pin "1") (pinfunction "1_1") (pintype "passive"))
      (node (ref "R19") (pin "2") (pinfunction "2_2") (pintype "passive"))
      (node (ref "R2") (pin "1") (pinfunction "1_1") (pintype "passive"))
      (node (ref "R20") (pin "2") (pinfunction "2_2") (pintype "passive"))
      (node (ref "R22") (pin "2") (pinfunction "2_2") (pintype "passive"))
      (node (ref "R24") (pin "2") (pinfunction "2_2") (pintype "passive"))
      (node (ref "R26") (pin "1") (pinfunction "1_1") (pintype "passive"))
      (node (ref "R3") (pin "1") (pinfunction "1_1") (pintype "passive"))
      (node (ref "R5") (pin "1") (pinfunction "1_1") (pintype "passive"))
      (node (ref "R6") (pin "1") (pinfunction "1_1") (pintype "passive"))
      (node (ref "R9") (pin "2") (pinfunction "2_2") (pintype "passive"))
      (node (ref "TP41") (pin "1") (pinfunction "TP_1") (pintype "passive"))
      (node (ref "TP6") (pin "1") (pinfunction "TP_1") (pintype "passive"))
      (node (ref "TP8") (pin "1") (pinfunction "TP_1") (pintype "passive"))
      (node (ref "TP9") (pin "1") (pinfunction "TP_1") (pintype "passive"))
      (node (ref "U10") (pin "6") (pinfunction "VOS_6") (pintype "input"))
      (node (ref "U2") (pin "2") (pinfunction "3V3_2") (pintype "power_in"))
      (node (ref "U8") (pin "6") (pinfunction "VDD_6") (pintype "power_in"))
      (node (ref "U9") (pin "13") (pinfunction "VDD_13") (pintype "power_in"))
      (node (ref "U9") (pin "8") (pinfunction "VLOGIC_8") (pintype "power_in"))
    )
    (net (code "2") (name "+GND") (class "Default")
      (node (ref "C1") (pin "1") (pinfunction "1_1") (pintype "passive"))
      (node (ref "C10") (pin "1") (pinfunction "1_1") (pintype "passive"))
      (node (ref "C11") (pin "2") (pinfunction "2_2") (pintype "passive"))
      (node (ref "C12") (pin "1") (pinfunction "1_1") (pintype "passive"))
      (node (ref "C13") (pin "2") (pinfunction "2_2") (pintype "passive"))
      (node (ref "C14") (pin "2") (pinfunction "2_2") (pintype "passive"))
      (node (ref "C15") (pin "1") (pinfunction "1_1") (pintype "passive"))
      (node (ref "C16") (pin "2") (pinfunction "2_2") (pintype "passive"))
      (node (ref "C17") (pin "1") (pinfunction "1_1") (pintype "passive"))
      (node (ref "C18") (pin "2") (pinfunction "2_2") (pintype "passive"))
      (node (ref "C19") (pin "1") (pinfunction "1_1") (pintype "passive"))
      (node (ref "C2") (pin "1") (pinfunction "1_1") (pintype "passive"))
      (node (ref "C20") (pin "2") (pinfunction "2_2") (pintype "passive"))
      (node (ref "C21") (pin "2") (pinfunction "2_2") (pintype "passive"))
      (node (ref "C22") (pin "2") (pinfunction "2_2") (pintype "passive"))
      (node (ref "C4") (pin "1") (pinfunction "1_1") (pintype "passive"))
      (node (ref "C5") (pin "1") (pinfunction "1_1") (pintype "passive"))
      (node (ref "C6") (pin "1") (pinfunction "1_1") (pintype "passive"))
      (node (ref "C7") (pin "1") (pinfunction "1_1") (pintype "passive"))
      (node (ref "C8") (pin "1") (pinfunction "1_1") (pintype "passive"))
      (node (ref "J1") (pin "6") (pinfunction "6_6") (pintype "passive"))
      (node (ref "J2") (pin "A1") (pinfunction "GND1_A1") (pintype "passive"))
      (node (ref "J2") (pin "A12") (pinfunction "GND2_A12") (pintype "passive"))
      (node (ref "J2") (pin "B1") (pinfunction "GND3_B1") (pintype "passive"))
      (node (ref "J2") (pin "B12") (pinfunction "GND4_B12") (pintype "passive"))
      (node (ref "J2") (pin "S1") (pinfunction "SHIELD_S1") (pintype "passive"))
      (node (ref "J2") (pin "S2") (pinfunction "SHIELD_S2") (pintype "passive"))
      (node (ref "J2") (pin "S3") (pinfunction "SHIELD_S3") (pintype "passive"))
      (node (ref "J2") (pin "S4") (pinfunction "SHIELD_S4") (pintype "passive"))
      (node (ref "J3") (pin "1") (pinfunction "GND_1") (pintype "passive"))
      (node (ref "J3") (pin "2") (pinfunction "GND_2") (pintype "passive"))
      (node (ref "J3") (pin "3") (pinfunction "GND_3") (pintype "passive"))
      (node (ref "J3") (pin "8") (pinfunction "GND_8") (pintype "passive"))
      (node (ref "J4") (pin "4") (pinfunction "4_4") (pintype "passive"))
      (node (ref "R10") (pin "2") (pinfunction "2_2") (pintype "passive"))
      (node (ref "R14") (pin "1") (pinfunction "1_1") (pintype "passive"))
      (node (ref "R15") (pin "1") (pinfunction "1_1") (pintype "passive"))
      (node (ref "R25") (pin "1") (pinfunction "1_1") (pintype "passive"))
      (node (ref "R27") (pin "1") (pinfunction "1_1") (pintype "passive"))
      (node (ref "R28") (pin "2") (pinfunction "2_2") (pintype "passive"))
      (node (ref "R4") (pin "1") (pinfunction "1_1") (pintype "passive"))
      (node (ref "R7") (pin "2") (pinfunction "2_2") (pintype "passive"))
      (node (ref "S4") (pin "1") (pinfunction "1_1") (pintype "passive"))
      (node (ref "S4") (pin "3") (pinfunction "3_3") (pintype "passive"))
      (node (ref "S5") (pin "1") (pinfunction "1_1") (pintype "passive"))
      (node (ref "S5") (pin "3") (pinfunction "3_3") (pintype "passive"))
      (node (ref "S6") (pin "1") (pinfunction "1_1") (pintype "passive"))
      (node (ref "S6") (pin "3") (pinfunction "3_3") (pintype "passive"))
      (node (ref "TP11") (pin "1") (pinfunction "TP_1") (pintype "passive"))
      (node (ref "TP38") (pin "1") (pinfunction "TP_1") (pintype "passive"))
      (node (ref "U10") (pin "1") (pinfunction "PGND_1") (pintype "power_in"))
      (node (ref "U10") (pin "4") (pinfunction "AGND_4") (pintype "power_in"))
      (node (ref "U10") (pin "5") (pinfunction "FB_5") (pintype "input"))
      (node (ref "U10") (pin "9") (pinfunction "EXP_9") (pintype "passive"))
      (node (ref "U2") (pin "1") (pinfunction "GND_1") (pintype "power_in"))
      (node (ref "U2") (pin "15") (pinfunction "GND_15") (pintype "power_in"))
      (node (ref "U2") (pin "38") (pinfunction "GND_38") (pintype "power_in"))
      (node (ref "U2") (pin "39_1") (pinfunction "GND_39_1") (pintype "power_in"))
      (node (ref "U2") (pin "39_10") (pinfunction "GND_39_10") (pintype "power_in"))
      (node (ref "U2") (pin "39_11") (pinfunction "GND_39_11") (pintype "power_in"))
      (node (ref "U2") (pin "39_12") (pinfunction "GND_39_12") (pintype "power_in"))
      (node (ref "U2") (pin "39_13") (pinfunction "GND_39_13") (pintype "power_in"))
      (node (ref "U2") (pin "39_14") (pinfunction "GND_39_14") (pintype "power_in"))
      (node (ref "U2") (pin "39_15") (pinfunction "GND_39_15") (pintype "power_in"))
      (node (ref "U2") (pin "39_16") (pinfunction "GND_39_16") (pintype "power_in"))
      (node (ref "U2") (pin "39_17") (pinfunction "GND_39_17") (pintype "power_in"))
      (node (ref "U2") (pin "39_18") (pinfunction "GND_39_18") (pintype "power_in"))
      (node (ref "U2") (pin "39_19") (pinfunction "GND_39_19") (pintype "power_in"))
      (node (ref "U2") (pin "39_2") (pinfunction "GND_39_2") (pintype "power_in"))
      (node (ref "U2") (pin "39_20") (pinfunction "GND_39_20") (pintype "power_in"))
      (node (ref "U2") (pin "39_21") (pinfunction "GND_39_21") (pintype "power_in"))
      (node (ref "U2") (pin "39_3") (pinfunction "GND_39_3") (pintype "power_in"))
      (node (ref "U2") (pin "39_4") (pinfunction "GND_39_4") (pintype "power_in"))
      (node (ref "U2") (pin "39_5") (pinfunction "GND_39_5") (pintype "power_in"))
      (node (ref "U2") (pin "39_6") (pinfunction "GND_39_6") (pintype "power_in"))
      (node (ref "U2") (pin "39_7") (pinfunction "GND_39_7") (pintype "power_in"))
      (node (ref "U2") (pin "39_8") (pinfunction "GND_39_8") (pintype "power_in"))
      (node (ref "U2") (pin "39_9") (pinfunction "GND_39_9") (pintype "power_in"))
      (node (ref "U3") (pin "1") (pinfunction "S1_1") (pintype "passive"))
      (node (ref "U4") (pin "3") (pinfunction "S_3") (pintype "passive"))
      (node (ref "U5") (pin "14") (pinfunction "TMR_14") (pintype "input"))
      (node (ref "U5") (pin "17") (pinfunction "EXP_17") (pintype "power_in"))
      (node (ref "U5") (pin "4") (pinfunction "~{CE}_4") (pintype "input"))
      (node (ref "U5") (pin "6") (pinfunction "EN1_6") (pintype "input"))
      (node (ref "U5") (pin "8") (pinfunction "VSS_8") (pintype "power_in"))
      (node (ref "U7") (pin "10") (pinfunction "GND_10") (pintype "power_in"))
      (node (ref "U7") (pin "5") (pinfunction "GND_5") (pintype "power_in"))
      (node (ref "U7") (pin "8") (pinfunction "GND_8") (pintype "power_in"))
      (node (ref "U8") (pin "7") (pinfunction "GND_7") (pintype "power_in"))
      (node (ref "U9") (pin "1") (pinfunction "CLKIN_1") (pintype "input"))
      (node (ref "U9") (pin "11") (pinfunction "FSYNC_11") (pintype "input"))
      (node (ref "U9") (pin "9") (pinfunction "AD0_9") (pintype "input"))
    )
    (net (code "3") (name "+VPMIC") (class "Default")
      (node (ref "C10") (pin "2") (pinfunction "2_2") (pintype "passive"))
      (node (ref "C17") (pin "2") (pinfunction "2_2") (pintype "passive"))
      (node (ref "C5") (pin "2") (pinfunction "2_2") (pintype "passive"))
      (node (ref "TP15") (pin "1") (pinfunction "TP_1") (pintype "passive"))
      (node (ref "U10") (pin "2") (pinfunction "VIN_2") (pintype "input"))
      (node (ref "U10") (pin "3") (pinfunction "EN_3") (pintype "input"))
      (node (ref "U5") (pin "10") (pinfunction "OUT_10_10") (pintype "output"))
      (node (ref "U5") (pin "11") (pinfunction "OUT_11_11") (pintype "output"))
      (node (ref "U5") (pin "5") (pinfunction "EN2_5") (pintype "input"))
      (node (ref "U7") (pin "7") (pinfunction "VDD_7") (pintype "power_in"))
    )
    (net (code "4") (name "/+5VUSB") (class "Default")
      (node (ref "C4") (pin "2") (pinfunction "2_2") (pintype "passive"))
      (node (ref "J2") (pin "A4") (pinfunction "VBUS1_A4") (pintype "passive"))
      (node (ref "J2") (pin "A9") (pinfunction "VBUS2_A9") (pintype "passive"))
      (node (ref "J2") (pin "B4") (pinfunction "VBUS3_B4") (pintype "passive"))
      (node (ref "J2") (pin "B9") (pinfunction "VBUS4_B9") (pintype "passive"))
      (node (ref "TP31") (pin "1") (pinfunction "TP_1") (pintype "passive"))
      (node (ref "U5") (pin "13") (pinfunction "IN_13") (pintype "input"))
    )
    (net (code "5") (name "/AUDIO_AMP_IN") (class "Default")
      (node (ref "C9") (pin "1") (pinfunction "1_1") (pintype "passive"))
      (node (ref "TP30") (pin "1") (pinfunction "TP_1") (pintype "passive"))
      (node (ref "U2") (pin "16") (pinfunction "IO13_16") (pintype "bidirectional"))
    )
    (net (code "6") (name "/BAT+") (class "Default")
      (node (ref "C6") (pin "2") (pinfunction "2_2") (pintype "passive"))
      (node (ref "R1") (pin "2") (pinfunction "2_2") (pintype "passive"))
      (node (ref "U5") (pin "2") (pinfunction "BAT_2_2") (pintype "bidirectional"))
      (node (ref "U5") (pin "3") (pinfunction "BAT_3_3") (pintype "bidirectional"))
      (node (ref "U6") (pin "1") (pinfunction "+_1") (pintype "passive"))
    )
    (net (code "7") (name "/BAT-") (class "Default")
      (node (ref "C3") (pin "1") (pinfunction "1_1") (pintype "passive"))
      (node (ref "R8") (pin "1") (pinfunction "1_1") (pintype "passive"))
      (node (ref "U1") (pin "4") (pinfunction "VSS_4") (pintype "passive"))
      (node (ref "U3") (pin "3") (pinfunction "S2_3") (pintype "passive"))
      (node (ref "U6") (pin "2") (pinfunction "-_2") (pintype "passive"))
    )
    (net (code "8") (name "/BUTTON") (class "Default")
      (node (ref "C22") (pin "1") (pinfunction "1_1") (pintype "passive"))
      (node (ref "S6") (pin "2") (pinfunction "2_2") (pintype "passive"))
      (node (ref "S6") (pin "4") (pinfunction "4_4") (pintype "passive"))
      (node (ref "TP45") (pin "1") (pinfunction "TP_1") (pintype "passive"))
      (node (ref "U2") (pin "6") (pinfunction "IO34_6") (pintype "input"))
    )
    (net (code "9") (name "/CHAR_CHG") (class "Default")
      (node (ref "TP13") (pin "1") (pinfunction "TP_1") (pintype "passive"))
      (node (ref "U2") (pin "4") (pinfunction "SENSOR_VP_4") (pintype "input"))
      (node (ref "U5") (pin "9") (pinfunction "~{CHG}_9") (pintype "output"))
    )
    (net (code "10") (name "/CHAR_PGOOD") (class "Default")
      (node (ref "TP14") (pin "1") (pinfunction "TP_1") (pintype "passive"))
      (node (ref "U2") (pin "5") (pinfunction "SENSOR_VN_5") (pintype "input"))
      (node (ref "U5") (pin "7") (pinfunction "~{PGOOD}_7") (pintype "output"))
    )
    (net (code "11") (name "/DEBUG") (class "Default")
      (node (ref "TP2") (pin "1") (pinfunction "TP_1") (pintype "passive"))
      (node (ref "U2") (pin "24") (pinfunction "IO2_24") (pintype "bidirectional"))
    )
    (net (code "12") (name "/DTR") (class "Default")
      (node (ref "J1") (pin "4") (pinfunction "4_4") (pintype "passive"))
      (node (ref "J4") (pin "2") (pinfunction "2_2") (pintype "passive"))
      (node (ref "Q2") (pin "2") (pinfunction "E_2") (pintype "passive"))
      (node (ref "R21") (pin "1") (pinfunction "1_1") (pintype "passive"))
      (node (ref "TP5") (pin "1") (pinfunction "TP_1") (pintype "passive"))
    )
    (net (code "13") (name "/ESP32_BOOT") (class "Default")
      (node (ref "C13") (pin "1") (pinfunction "1_1") (pintype "passive"))
      (node (ref "Q2") (pin "3") (pinfunction "C_3") (pintype "passive"))
      (node (ref "S4") (pin "2") (pinfunction "2_2") (pintype "passive"))
      (node (ref "S4") (pin "4") (pinfunction "4_4") (pintype "passive"))
      (node (ref "TP39") (pin "1") (pinfunction "TP_1") (pintype "passive"))
      (node (ref "U2") (pin "25") (pinfunction "IO0_25") (pintype "bidirectional"))
    )
    (net (code "14") (name "/ESP32_EN") (class "Default")
      (node (ref "C15") (pin "2") (pinfunction "2_2") (pintype "passive"))
      (node (ref "C18") (pin "1") (pinfunction "1_1") (pintype "passive"))
      (node (ref "Q1") (pin "3") (pinfunction "C_3") (pintype "passive"))
      (node (ref "R22") (pin "1") (pinfunction "1_1") (pintype "passive"))
      (node (ref "S5") (pin "2") (pinfunction "2_2") (pintype "passive"))
      (node (ref "S5") (pin "4") (pinfunction "4_4") (pintype "passive"))
      (node (ref "TP40") (pin "1") (pinfunction "TP_1") (pintype "passive"))
      (node (ref "U2") (pin "3") (pinfunction "EN_3") (pintype "input"))
    )
    (net (code "15") (name "/ESP32_RXD0") (class "Default")
      (node (ref "J1") (pin "3") (pinfunction "3_3") (pintype "passive"))
      (node (ref "J4") (pin "6") (pinfunction "6_6") (pintype "passive"))
      (node (ref "TP4") (pin "1") (pinfunction "TP_1") (pintype "passive"))
      (node (ref "U2") (pin "34") (pinfunction "RXD0_34") (pintype "bidirectional"))
    )
    (net (code "16") (name "/ESP32_TXD0") (class "Default")
      (node (ref "J1") (pin "2") (pinfunction "2_2") (pintype "passive"))
      (node (ref "J4") (pin "5") (pinfunction "5_5") (pintype "passive"))
      (node (ref "TP3") (pin "1") (pinfunction "TP_1") (pintype "passive"))
      (node (ref "U2") (pin "35") (pinfunction "TXD0_35") (pintype "bidirectional"))
    )
    (net (code "17") (name "/I2C_SCL") (class "Default")
      (node (ref "J3") (pin "7") (pinfunction "CTP_SCL_7") (pintype "passive"))
      (node (ref "R20") (pin "1") (pinfunction "1_1") (pintype "passive"))
      (node (ref "TP26") (pin "1") (pinfunction "TP_1") (pintype "passive"))
      (node (ref "TP43") (pin "1") (pinfunction "TP_1") (pintype "passive"))
      (node (ref "U2") (pin "12") (pinfunction "IO27_12") (pintype "bidirectional"))
      (node (ref "U9") (pin "23") (pinfunction "SCL_23") (pintype "input"))
    )
    (net (code "18") (name "/I2C_SDA") (class "Default")
      (node (ref "J3") (pin "6") (pinfunction "CTP_SDA_6") (pintype "passive"))
      (node (ref "R19") (pin "1") (pinfunction "1_1") (pintype "passive"))
      (node (ref "TP27") (pin "1") (pinfunction "TP_1") (pintype "passive"))
      (node (ref "TP44") (pin "1") (pinfunction "TP_1") (pintype "passive"))
      (node (ref "U2") (pin "11") (pinfunction "IO26_11") (pintype "bidirectional"))
      (node (ref "U9") (pin "24") (pinfunction "SDA_24") (pintype "bidirectional"))
    )
    (net (code "19") (name "/IMU_INT") (class "Default")
      (node (ref "TP42") (pin "1") (pinfunction "TP_1") (pintype "passive"))
      (node (ref "U2") (pin "7") (pinfunction "IO35_7") (pintype "input"))
      (node (ref "U9") (pin "12") (pinfunction "INT_12") (pintype "output"))
    )
    (net (code "20") (name "/LCD_CS") (class "Default")
      (node (ref "J3") (pin "13") (pinfunction "CS_13") (pintype "passive"))
      (node (ref "TP24") (pin "1") (pinfunction "TP_1") (pintype "passive"))
      (node (ref "U2") (pin "33") (pinfunction "IO21_33") (pintype "bidirectional"))
    )
    (net (code "21") (name "/LCD_LEDK") (class "Default")
      (node (ref "J3") (pin "50") (pinfunction "LEDK_50") (pintype "passive"))
      (node (ref "TP1") (pin "1") (pinfunction "TP_1") (pintype "passive"))
      (node (ref "U4") (pin "1") (pinfunction "D_1") (pintype "passive"))
    )
    (net (code "22") (name "/LCD_LEDS") (class "Default")
      (node (ref "R9") (pin "1") (pinfunction "1_1") (pintype "passive"))
      (node (ref "TP12") (pin "1") (pinfunction "TP_1") (pintype "passive"))
      (node (ref "U2") (pin "26") (pinfunction "IO4_26") (pintype "bidirectional"))
      (node (ref "U4") (pin "2") (pinfunction "G_2") (pintype "passive"))
    )
    (net (code "23") (name "/LCD_RD") (class "Default")
      (node (ref "J3") (pin "16") (pinfunction "RD_16") (pintype "passive"))
      (node (ref "TP20") (pin "1") (pinfunction "TP_1") (pintype "passive"))
      (node (ref "U2") (pin "29") (pinfunction "IO5_29") (pintype "bidirectional"))
    )
    (net (code "24") (name "/LCD_RESET") (class "Default")
      (node (ref "J3") (pin "4") (pinfunction "CTP_RES_4") (pintype "passive"))
      (node (ref "J3") (pin "41") (pinfunction "RESET_41") (pintype "passive"))
      (node (ref "TP29") (pin "1") (pinfunction "TP_1") (pintype "passive"))
      (node (ref "U2") (pin "23") (pinfunction "IO15_23") (pintype "bidirectional"))
    )
    (net (code "25") (name "/LCD_RS_SCL") (class "Default")
      (node (ref "J3") (pin "14") (pinfunction "RS_SCL_14") (pintype "passive"))
      (node (ref "TP23") (pin "1") (pinfunction "TP_1") (pintype "passive"))
      (node (ref "U2") (pin "31") (pinfunction "IO19_31") (pintype "bidirectional"))
    )
    (net (code "26") (name "/LCD_SDI") (class "Default")
      (node (ref "J3") (pin "17") (pinfunction "SDI_17") (pintype "passive"))
      (node (ref "TP19") (pin "1") (pinfunction "TP_1") (pintype "passive"))
      (node (ref "U2") (pin "28") (pinfunction "IO17_28") (pintype "bidirectional"))
    )
    (net (code "27") (name "/LCD_SDO") (class "Default")
      (node (ref "J3") (pin "18") (pinfunction "SDO_18") (pintype "passive"))
      (node (ref "TP17") (pin "1") (pinfunction "TP_1") (pintype "passive"))
      (node (ref "U2") (pin "27") (pinfunction "IO16_27") (pintype "bidirectional"))
    )
    (net (code "28") (name "/LCD_TE") (class "Default")
      (node (ref "J3") (pin "12") (pinfunction "TE_12") (pintype "passive"))
      (node (ref "TP25") (pin "1") (pinfunction "TP_1") (pintype "passive"))
      (node (ref "U2") (pin "36") (pinfunction "IO22_36") (pintype "bidirectional"))
    )
    (net (code "29") (name "/LCD_TOUCH_IRQ") (class "Default")
      (node (ref "J3") (pin "5") (pinfunction "CTP_IRQ_5") (pintype "passive"))
      (node (ref "TP28") (pin "1") (pinfunction "TP_1") (pintype "passive"))
      (node (ref "U2") (pin "37") (pinfunction "IO23_37") (pintype "bidirectional"))
    )
    (net (code "30") (name "/LCD_WR_RS") (class "Default")
      (node (ref "J3") (pin "15") (pinfunction "WR_RS_15") (pintype "passive"))
      (node (ref "TP21") (pin "1") (pinfunction "TP_1") (pintype "passive"))
      (node (ref "U2") (pin "30") (pinfunction "IO18_30") (pintype "bidirectional"))
    )
    (net (code "31") (name "/LED_B") (class "Default")
      (node (ref "R13") (pin "2") (pinfunction "2_2") (pintype "passive"))
      (node (ref "TP22") (pin "1") (pinfunction "TP_1") (pintype "passive"))
      (node (ref "U2") (pin "8") (pinfunction "IO32_8") (pintype "bidirectional"))
    )
    (net (code "32") (name "/LED_G") (class "Default")
      (node (ref "R12") (pin "2") (pinfunction "2_2") (pintype "passive"))
      (node (ref "TP18") (pin "1") (pinfunction "TP_1") (pintype "passive"))
      (node (ref "U2") (pin "9") (pinfunction "IO33_9") (pintype "bidirectional"))
    )
    (net (code "33") (name "/LED_R") (class "Default")
      (node (ref "R11") (pin "2") (pinfunction "2_2") (pintype "passive"))
      (node (ref "TP16") (pin "1") (pinfunction "TP_1") (pintype "passive"))
      (node (ref "U2") (pin "10") (pinfunction "IO25_10") (pintype "bidirectional"))
    )
    (net (code "34") (name "/MOTOR+") (class "Default")
      (node (ref "M1") (pin "2+") (pinfunction "P2+_2+") (pintype "bidirectional"))
      (node (ref "TP37") (pin "1") (pinfunction "TP_1") (pintype "passive"))
      (node (ref "U7") (pin "9") (pinfunction "OUT_P_9") (pintype "output"))
    )
    (net (code "35") (name "/MOTOR-") (class "Default")
      (node (ref "M1") (pin "1-") (pinfunction "P1-_1-") (pintype "bidirectional"))
      (node (ref "TP36") (pin "1") (pinfunction "TP_1") (pintype "passive"))
      (node (ref "U7") (pin "6") (pinfunction "OUT_M_6") (pintype "output"))
    )
    (net (code "36") (name "/MOTOR_EN") (class "Default")
      (node (ref "TP32") (pin "1") (pinfunction "TP_1") (pintype "passive"))
      (node (ref "U2") (pin "14") (pinfunction "IO12_14") (pintype "bidirectional"))
      (node (ref "U7") (pin "1") (pinfunction "EN_1") (pintype "input"))
    )
    (net (code "37") (name "/MOTOR_PWM") (class "Default")
      (node (ref "TP33") (pin "1") (pinfunction "TP_1") (pintype "passive"))
      (node (ref "U2") (pin "13") (pinfunction "IO14_13") (pintype "bidirectional"))
      (node (ref "U7") (pin "2") (pinfunction "PWM_2") (pintype "input"))
    )
    (net (code "38") (name "/RTS") (class "Default")
      (node (ref "J1") (pin "5") (pinfunction "5_5") (pintype "passive"))
      (node (ref "J4") (pin "3") (pinfunction "3_3") (pintype "passive"))
      (node (ref "Q1") (pin "2") (pinfunction "E_2") (pintype "passive"))
      (node (ref "R23") (pin "1") (pinfunction "1_1") (pintype "passive"))
      (node (ref "TP10") (pin "1") (pinfunction "TP_1") (pintype "passive"))
    )
    (net (code "39") (name "/SPEAKER_+") (class "Default")
      (node (ref "R16") (pin "2") (pinfunction "2_2") (pintype "passive"))
      (node (ref "TP34") (pin "1") (pinfunction "TP_1") (pintype "passive"))
      (node (ref "U8") (pin "5") (pinfunction "VO1_5") (pintype "output"))
    )
    (net (code "40") (name "/SPEAKER_-") (class "Default")
      (node (ref "TP35") (pin "1") (pinfunction "TP_1") (pintype "passive"))
      (node (ref "U8") (pin "8") (pinfunction "VO2_8") (pintype "output"))
    )
    (net (code "41") (name "Net-(C9-Pad2)") (class "Default")
      (node (ref "C9") (pin "2") (pinfunction "2_2") (pintype "passive"))
      (node (ref "R17") (pin "1") (pinfunction "1_1") (pintype "passive"))
    )
    (net (code "42") (name "Net-(J3-IM0)") (class "Default")
      (node (ref "J3") (pin "45") (pinfunction "IM0_45") (pintype "passive"))
      (node (ref "R28") (pin "1") (pinfunction "1_1") (pintype "passive"))
      (node (ref "TP7") (pin "1") (pinfunction "TP_1") (pintype "passive"))
    )
    (net (code "43") (name "Net-(J3-LED-A1)") (class "Default")
      (node (ref "J3") (pin "49") (pinfunction "LED-A1_49") (pintype "passive"))
      (node (ref "R2") (pin "2") (pinfunction "2_2") (pintype "passive"))
    )
    (net (code "44") (name "Net-(J3-LED-A2)") (class "Default")
      (node (ref "J3") (pin "48") (pinfunction "LED-A2_48") (pintype "passive"))
      (node (ref "R3") (pin "2") (pinfunction "2_2") (pintype "passive"))
    )
    (net (code "45") (name "Net-(J3-LED-A3)") (class "Default")
      (node (ref "J3") (pin "47") (pinfunction "LED-A3_47") (pintype "passive"))
      (node (ref "R5") (pin "2") (pinfunction "2_2") (pintype "passive"))
    )
    (net (code "46") (name "Net-(J3-LED-A4)") (class "Default")
      (node (ref "J3") (pin "46") (pinfunction "LED-A4_46") (pintype "passive"))
      (node (ref "R6") (pin "2") (pinfunction "2_2") (pintype "passive"))
    )
    (net (code "47") (name "Net-(LED1-B)") (class "Default")
      (node (ref "LED1") (pin "3") (pinfunction "B_3") (pintype "passive"))
      (node (ref "R13") (pin "1") (pinfunction "1_1") (pintype "passive"))
    )
    (net (code "48") (name "Net-(LED1-G)") (class "Default")
      (node (ref "LED1") (pin "2") (pinfunction "G_2") (pintype "passive"))
      (node (ref "R12") (pin "1") (pinfunction "1_1") (pintype "passive"))
    )
    (net (code "49") (name "Net-(LED1-R)") (class "Default")
      (node (ref "LED1") (pin "1") (pinfunction "R_1") (pintype "passive"))
      (node (ref "R11") (pin "1") (pinfunction "1_1") (pintype "passive"))
    )
    (net (code "50") (name "Net-(Q1-B)") (class "Default")
      (node (ref "Q1") (pin "1") (pinfunction "B_1") (pintype "passive"))
      (node (ref "R21") (pin "2") (pinfunction "2_2") (pintype "passive"))
    )
    (net (code "51") (name "Net-(Q2-B)") (class "Default")
      (node (ref "Q2") (pin "1") (pinfunction "B_1") (pintype "passive"))
      (node (ref "R23") (pin "2") (pinfunction "2_2") (pintype "passive"))
    )
    (net (code "52") (name "Net-(U1-BAT)") (class "Default")
      (node (ref "C3") (pin "2") (pinfunction "2_2") (pintype "passive"))
      (node (ref "R1") (pin "1") (pinfunction "1_1") (pintype "passive"))
      (node (ref "U1") (pin "5") (pinfunction "BAT_5") (pintype "passive"))
    )
    (net (code "53") (name "Net-(U1-COUT)") (class "Default")
      (node (ref "R7") (pin "1") (pinfunction "1_1") (pintype "passive"))
      (node (ref "U1") (pin "2") (pinfunction "COUT_2") (pintype "passive"))
      (node (ref "U3") (pin "2") (pinfunction "G1_2") (pintype "passive"))
    )
    (net (code "54") (name "Net-(U1-DOUT)") (class "Default")
      (node (ref "R8") (pin "2") (pinfunction "2_2") (pintype "passive"))
      (node (ref "U1") (pin "3") (pinfunction "DOUT_3") (pintype "passive"))
      (node (ref "U3") (pin "4") (pinfunction "G2_4") (pintype "passive"))
    )
    (net (code "55") (name "Net-(U1-V-)") (class "Default")
      (node (ref "R4") (pin "2") (pinfunction "2_2") (pintype "passive"))
      (node (ref "U1") (pin "6") (pinfunction "V-_6") (pintype "passive"))
    )
    (net (code "56") (name "Net-(U3-D-Pad5)") (class "Default")
      (node (ref "U3") (pin "5") (pinfunction "D_5") (pintype "passive"))
      (node (ref "U3") (pin "6") (pinfunction "D_6") (pintype "passive"))
      (node (ref "U3") (pin "7") (pinfunction "D_7") (pintype "passive"))
      (node (ref "U3") (pin "8") (pinfunction "D_8") (pintype "passive"))
    )
    (net (code "57") (name "Net-(U5-ILIM)") (class "Default")
      (node (ref "R14") (pin "2") (pinfunction "2_2") (pintype "passive"))
      (node (ref "U5") (pin "12") (pinfunction "ILIM_12") (pintype "input"))
    )
    (net (code "58") (name "Net-(U5-ISET)") (class "Default")
      (node (ref "R15") (pin "2") (pinfunction "2_2") (pintype "passive"))
      (node (ref "U5") (pin "16") (pinfunction "ISET_16") (pintype "bidirectional"))
    )
    (net (code "59") (name "Net-(U5-TS)") (class "Default")
      (node (ref "R10") (pin "1") (pinfunction "1_1") (pintype "passive"))
      (node (ref "U5") (pin "1") (pinfunction "TS_1") (pintype "input"))
    )
    (net (code "60") (name "Net-(U7-LRA{slash}!ERM)") (class "Default")
      (node (ref "R25") (pin "2") (pinfunction "2_2") (pintype "passive"))
      (node (ref "R26") (pin "2") (pinfunction "2_2") (pintype "passive"))
      (node (ref "U7") (pin "3") (pinfunction "LRA/!ERM_3") (pintype "input"))
    )
    (net (code "61") (name "Net-(U8-+IN)") (class "Default")
      (node (ref "C11") (pin "1") (pinfunction "1_1") (pintype "passive"))
      (node (ref "U8") (pin "2") (pinfunction "BYPASS_2") (pintype "input"))
      (node (ref "U8") (pin "3") (pinfunction "+IN_3") (pintype "input"))
    )
    (net (code "62") (name "Net-(U8--IN)") (class "Default")
      (node (ref "R16") (pin "1") (pinfunction "1_1") (pintype "passive"))
      (node (ref "R17") (pin "2") (pinfunction "2_2") (pintype "passive"))
      (node (ref "U8") (pin "4") (pinfunction "-IN_4") (pintype "input"))
    )
    (net (code "63") (name "Net-(U8-~{SHDN})") (class "Default")
      (node (ref "R18") (pin "2") (pinfunction "2_2") (pintype "passive"))
      (node (ref "R27") (pin "2") (pinfunction "2_2") (pintype "passive"))
      (node (ref "U8") (pin "1") (pinfunction "~{SHDN}_1") (pintype "input"))
    )
    (net (code "64") (name "Net-(U9-CPOUT)") (class "Default")
      (node (ref "C20") (pin "1") (pinfunction "1_1") (pintype "passive"))
      (node (ref "U9") (pin "20") (pinfunction "CPOUT_20") (pintype "passive"))
    )
    (net (code "65") (name "Net-(U9-REGOUT)") (class "Default")
      (node (ref "C21") (pin "1") (pinfunction "1_1") (pintype "passive"))
      (node (ref "U9") (pin "10") (pinfunction "REGOUT_10") (pintype "passive"))
    )
    (net (code "66") (name "Net-(U10-PG)") (class "Default")
      (node (ref "R24") (pin "1") (pinfunction "1_1") (pintype "passive"))
      (node (ref "U10") (pin "8") (pinfunction "PG_8") (pintype "output"))
    )
    (net (code "67") (name "Net-(U10-SW)") (class "Default")
      (node (ref "L1") (pin "1") (pinfunction "1_1") (pintype "passive"))
      (node (ref "U10") (pin "7") (pinfunction "SW_7") (pintype "output"))
    )
    (net (code "68") (name "unconnected-(J1-Pad1)") (class "Default")
      (node (ref "J1") (pin "1") (pinfunction "1_1") (pintype "passive+no_connect"))
    )
    (net (code "69") (name "unconnected-(J2-CC1-PadA5)") (class "Default")
      (node (ref "J2") (pin "A5") (pinfunction "CC1_A5") (pintype "passive+no_connect"))
    )
    (net (code "70") (name "unconnected-(J2-CC2-PadB5)") (class "Default")
      (node (ref "J2") (pin "B5") (pinfunction "CC2_B5") (pintype "passive+no_connect"))
    )
    (net (code "71") (name "unconnected-(J2-D1+-PadA6)") (class "Default")
      (node (ref "J2") (pin "A6") (pinfunction "D1+_A6") (pintype "passive+no_connect"))
    )
    (net (code "72") (name "unconnected-(J2-D1--PadA7)") (class "Default")
      (node (ref "J2") (pin "A7") (pinfunction "D1-_A7") (pintype "passive+no_connect"))
    )
    (net (code "73") (name "unconnected-(J2-D2+-PadB6)") (class "Default")
      (node (ref "J2") (pin "B6") (pinfunction "D2+_B6") (pintype "passive+no_connect"))
    )
    (net (code "74") (name "unconnected-(J2-D2--PadB7)") (class "Default")
      (node (ref "J2") (pin "B7") (pinfunction "D2-_B7") (pintype "passive+no_connect"))
    )
    (net (code "75") (name "unconnected-(J2-RX1+-PadB11)") (class "Default")
      (node (ref "J2") (pin "B11") (pinfunction "RX1+_B11") (pintype "passive+no_connect"))
    )
    (net (code "76") (name "unconnected-(J2-RX1--PadB10)") (class "Default")
      (node (ref "J2") (pin "B10") (pinfunction "RX1-_B10") (pintype "passive+no_connect"))
    )
    (net (code "77") (name "unconnected-(J2-RX2+-PadA11)") (class "Default")
      (node (ref "J2") (pin "A11") (pinfunction "RX2+_A11") (pintype "passive+no_connect"))
    )
    (net (code "78") (name "unconnected-(J2-RX2--PadA10)") (class "Default")
      (node (ref "J2") (pin "A10") (pinfunction "RX2-_A10") (pintype "passive+no_connect"))
    )
    (net (code "79") (name "unconnected-(J2-SBU1-PadA8)") (class "Default")
      (node (ref "J2") (pin "A8") (pinfunction "SBU1_A8") (pintype "passive+no_connect"))
    )
    (net (code "80") (name "unconnected-(J2-SBU2-PadB8)") (class "Default")
      (node (ref "J2") (pin "B8") (pinfunction "SBU2_B8") (pintype "passive+no_connect"))
    )
    (net (code "81") (name "unconnected-(J2-TX1+-PadA2)") (class "Default")
      (node (ref "J2") (pin "A2") (pinfunction "TX1+_A2") (pintype "passive+no_connect"))
    )
    (net (code "82") (name "unconnected-(J2-TX1--PadA3)") (class "Default")
      (node (ref "J2") (pin "A3") (pinfunction "TX1-_A3") (pintype "passive+no_connect"))
    )
    (net (code "83") (name "unconnected-(J2-TX2+-PadB2)") (class "Default")
      (node (ref "J2") (pin "B2") (pinfunction "TX2+_B2") (pintype "passive+no_connect"))
    )
    (net (code "84") (name "unconnected-(J2-TX2--PadB3)") (class "Default")
      (node (ref "J2") (pin "B3") (pinfunction "TX2-_B3") (pintype "passive+no_connect"))
    )
    (net (code "85") (name "unconnected-(J3-DB0-Pad19)") (class "Default")
      (node (ref "J3") (pin "19") (pinfunction "DB0_19") (pintype "passive+no_connect"))
    )
    (net (code "86") (name "unconnected-(J3-DB1-Pad20)") (class "Default")
      (node (ref "J3") (pin "20") (pinfunction "DB1_20") (pintype "passive+no_connect"))
    )
    (net (code "87") (name "unconnected-(J3-DB2-Pad21)") (class "Default")
      (node (ref "J3") (pin "21") (pinfunction "DB2_21") (pintype "passive+no_connect"))
    )
    (net (code "88") (name "unconnected-(J3-DB3-Pad22)") (class "Default")
      (node (ref "J3") (pin "22") (pinfunction "DB3_22") (pintype "passive+no_connect"))
    )
    (net (code "89") (name "unconnected-(J3-DB4-Pad23)") (class "Default")
      (node (ref "J3") (pin "23") (pinfunction "DB4_23") (pintype "passive+no_connect"))
    )
    (net (code "90") (name "unconnected-(J3-DB5-Pad24)") (class "Default")
      (node (ref "J3") (pin "24") (pinfunction "DB5_24") (pintype "passive+no_connect"))
    )
    (net (code "91") (name "unconnected-(J3-DB6-Pad25)") (class "Default")
      (node (ref "J3") (pin "25") (pinfunction "DB6_25") (pintype "passive+no_connect"))
    )
    (net (code "92") (name "unconnected-(J3-DB7-Pad26)") (class "Default")
      (node (ref "J3") (pin "26") (pinfunction "DB7_26") (pintype "passive+no_connect"))
    )
    (net (code "93") (name "unconnected-(J3-DB8-Pad27)") (class "Default")
      (node (ref "J3") (pin "27") (pinfunction "DB8_27") (pintype "passive+no_connect"))
    )
    (net (code "94") (name "unconnected-(J3-DB9-Pad28)") (class "Default")
      (node (ref "J3") (pin "28") (pinfunction "DB9_28") (pintype "passive+no_connect"))
    )
    (net (code "95") (name "unconnected-(J3-DB10-Pad29)") (class "Default")
      (node (ref "J3") (pin "29") (pinfunction "DB10_29") (pintype "passive+no_connect"))
    )
    (net (code "96") (name "unconnected-(J3-DB11-Pad30)") (class "Default")
      (node (ref "J3") (pin "30") (pinfunction "DB11_30") (pintype "passive+no_connect"))
    )
    (net (code "97") (name "unconnected-(J3-DB12-Pad31)") (class "Default")
      (node (ref "J3") (pin "31") (pinfunction "DB12_31") (pintype "passive+no_connect"))
    )
    (net (code "98") (name "unconnected-(J3-DB13-Pad32)") (class "Default")
      (node (ref "J3") (pin "32") (pinfunction "DB13_32") (pintype "passive+no_connect"))
    )
    (net (code "99") (name "unconnected-(J3-DB14-Pad33)") (class "Default")
      (node (ref "J3") (pin "33") (pinfunction "DB14_33") (pintype "passive+no_connect"))
    )
    (net (code "100") (name "unconnected-(J3-DB15-Pad34)") (class "Default")
      (node (ref "J3") (pin "34") (pinfunction "DB15_34") (pintype "passive+no_connect"))
    )
    (net (code "101") (name "unconnected-(J3-DB16-Pad35)") (class "Default")
      (node (ref "J3") (pin "35") (pinfunction "DB16_35") (pintype "passive+no_connect"))
    )
    (net (code "102") (name "unconnected-(J3-DB17-Pad36)") (class "Default")
      (node (ref "J3") (pin "36") (pinfunction "DB17_36") (pintype "passive+no_connect"))
    )
    (net (code "103") (name "unconnected-(J3-DE-Pad37)") (class "Default")
      (node (ref "J3") (pin "37") (pinfunction "DE_37") (pintype "passive+no_connect"))
    )
    (net (code "104") (name "unconnected-(J3-DOTCLK-Pad38)") (class "Default")
      (node (ref "J3") (pin "38") (pinfunction "DOTCLK_38") (pintype "passive+no_connect"))
    )
    (net (code "105") (name "unconnected-(J3-HSYNC-Pad39)") (class "Default")
      (node (ref "J3") (pin "39") (pinfunction "HSYNC_39") (pintype "passive+no_connect"))
    )
    (net (code "106") (name "unconnected-(J3-VSYNC-Pad40)") (class "Default")
      (node (ref "J3") (pin "40") (pinfunction "VSYNC_40") (pintype "passive+no_connect"))
    )
    (net (code "107") (name "unconnected-(J4-Pad1)") (class "Default")
      (node (ref "J4") (pin "1") (pinfunction "1_1") (pintype "passive+no_connect"))
    )
    (net (code "108") (name "unconnected-(M1-Sh1-Pad3)") (class "Default")
      (node (ref "M1") (pin "3") (pinfunction "Sh1_3") (pintype "passive"))
    )
    (net (code "109") (name "unconnected-(M1-Sh2-Pad4)") (class "Default")
      (node (ref "M1") (pin "4") (pinfunction "Sh2_4") (pintype "passive"))
    )
    (net (code "110") (name "unconnected-(U1-NC-Pad1)") (class "Default")
      (node (ref "U1") (pin "1") (pinfunction "NC_1") (pintype "passive+no_connect"))
    )
    (net (code "111") (name "unconnected-(U2-SCK{slash}CLK-Pad20)") (class "Default")
      (node (ref "U2") (pin "20") (pinfunction "SCK/CLK_20") (pintype "bidirectional+no_connect"))
    )
    (net (code "112") (name "unconnected-(U2-SCS{slash}CMD-Pad19)") (class "Default")
      (node (ref "U2") (pin "19") (pinfunction "SCS/CMD_19") (pintype "bidirectional+no_connect"))
    )
    (net (code "113") (name "unconnected-(U2-SDI{slash}SD1-Pad22)") (class "Default")
      (node (ref "U2") (pin "22") (pinfunction "SDI/SD1_22") (pintype "bidirectional+no_connect"))
    )
    (net (code "114") (name "unconnected-(U2-SDO{slash}SD0-Pad21)") (class "Default")
      (node (ref "U2") (pin "21") (pinfunction "SDO/SD0_21") (pintype "bidirectional+no_connect"))
    )
    (net (code "115") (name "unconnected-(U2-SHD{slash}SD2-Pad17)") (class "Default")
      (node (ref "U2") (pin "17") (pinfunction "SHD/SD2_17") (pintype "bidirectional+no_connect"))
    )
    (net (code "116") (name "unconnected-(U2-SWP{slash}SD3-Pad18)") (class "Default")
      (node (ref "U2") (pin "18") (pinfunction "SWP/SD3_18") (pintype "bidirectional+no_connect"))
    )
    (net (code "117") (name "unconnected-(U5-ITERM-Pad15)") (class "Default")
      (node (ref "U5") (pin "15") (pinfunction "ITERM_15") (pintype "input+no_connect"))
    )
    (net (code "118") (name "unconnected-(U7-NC-Pad4)") (class "Default")
      (node (ref "U7") (pin "4") (pinfunction "NC_4") (pintype "power_in+no_connect"))
    )
    (net (code "119") (name "unconnected-(U9-AUX_CL-Pad7)") (class "Default")
      (node (ref "U9") (pin "7") (pinfunction "AUX_CL_7") (pintype "input+no_connect"))
    )
    (net (code "120") (name "unconnected-(U9-AUX_DA-Pad6)") (class "Default")
      (node (ref "U9") (pin "6") (pinfunction "AUX_DA_6") (pintype "bidirectional+no_connect"))
    )
    (net (code "121") (name "unconnected-(U9-RESV-Pad22)") (class "Default")
      (node (ref "U9") (pin "22") (pinfunction "RESV_22") (pintype "passive+no_connect"))
    )
    (net (code "122") (name "unconnected-(U9-RESV@1-Pad19)") (class "Default")
      (node (ref "U9") (pin "19") (pinfunction "RESV@1_19") (pintype "passive+no_connect"))
    )
    (net (code "123") (name "unconnected-(U9-RESV@2-Pad21)") (class "Default")
      (node (ref "U9") (pin "21") (pinfunction "RESV@2_21") (pintype "passive+no_connect"))
    )
  )
)
